# Schematic_Wankler.net
KiCad netlist of a schematic drawn in EasyEDA
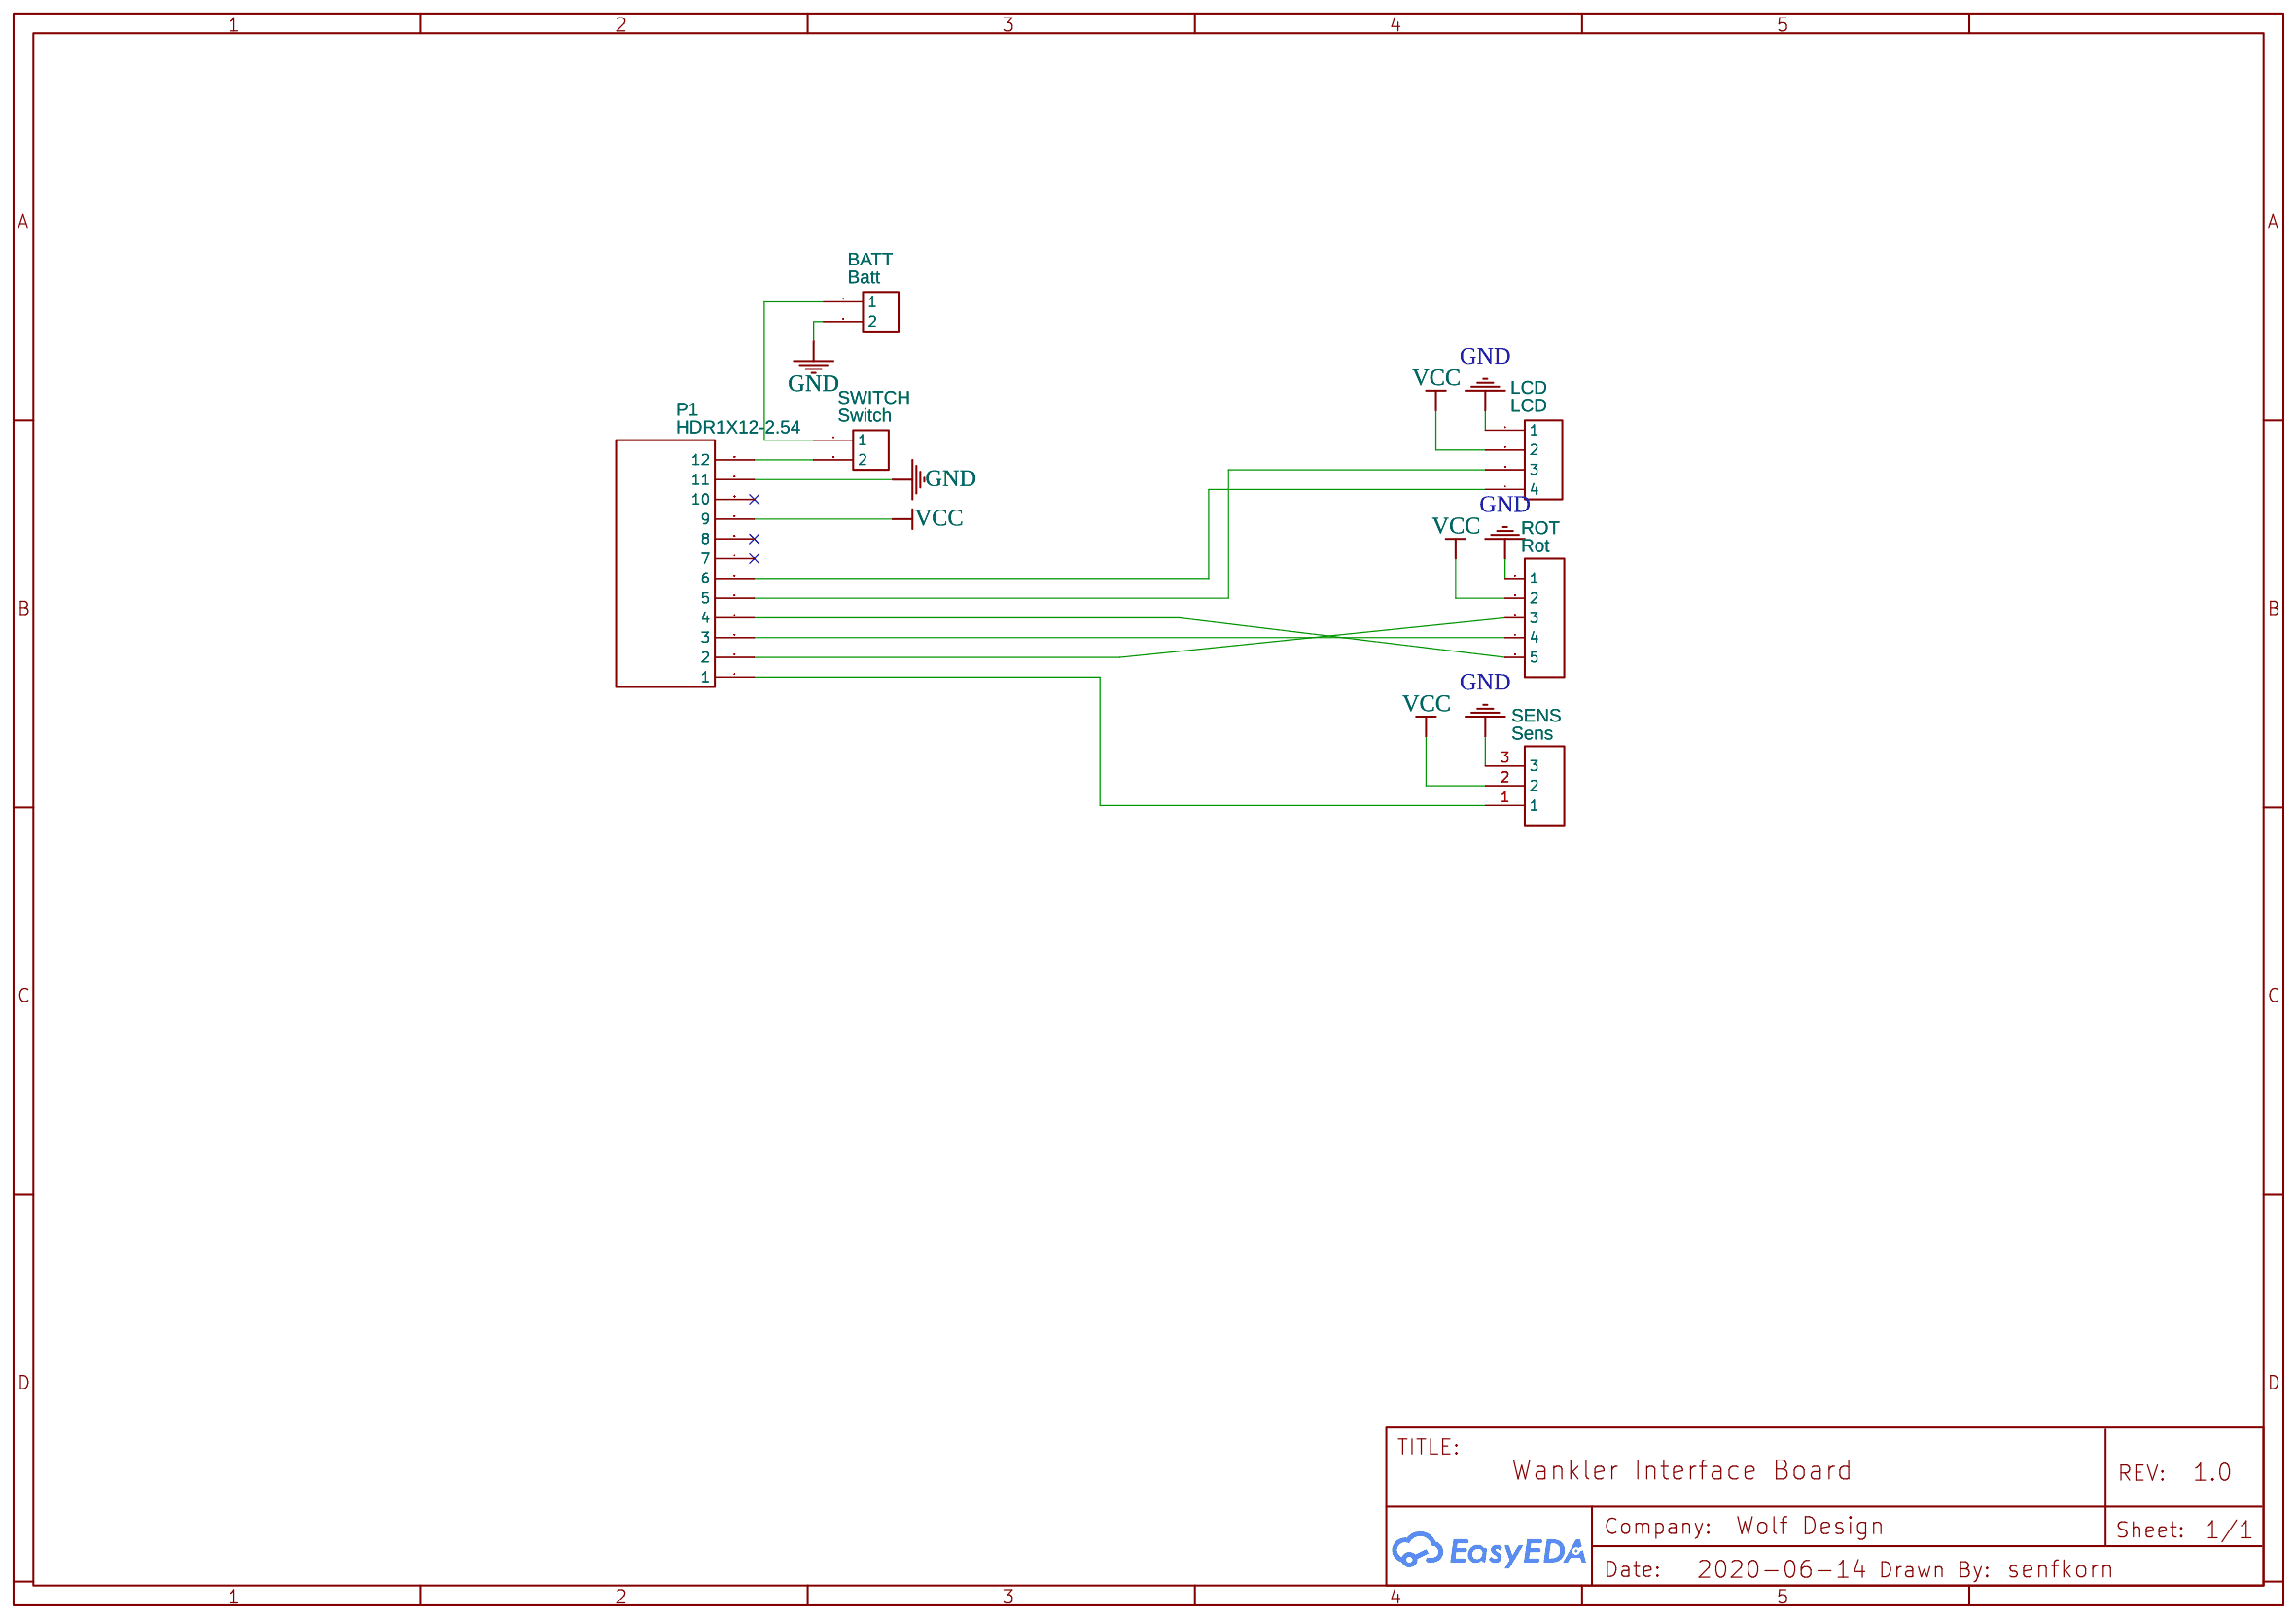
[diagram p0: schematic sheet]

(export (version "E")
  (design (tool "Eeschema 10.0.6"))
  (components
    (comp (ref "BATT") (value "Batt") (libsource (lib "") (part "HDR-2x1/2.54_1")))
    (comp (ref "LCD") (value "LCD") (libsource (lib "") (part "HDR-4x1/2.54")))
    (comp (ref "P1")
      (value "HDR1X12-2.54")
      (fields
        (field (name "BOM_Manufacturer Part") "Female headerHDR1X8-2.54")
        (field (name "BOM_Supplier Part") "C27438")
      )
      (libsource (lib "") (part "HDR1X12-2.54"))
    )
    (comp (ref "ROT")
      (value "Rot")
      (fields
        (field (name "BOM_Manufacturer Part") "2.54mm 1*5p Female header")
        (field (name "BOM_Supplier Part") "C50950")
      )
      (libsource (lib "") (part "HDR-2.54_1x5"))
    )
    (comp (ref "SENS") (value "Sens") (libsource (lib "") (part "HDR-3x1/2.54")))
    (comp (ref "SWITCH") (value "Switch") (libsource (lib "") (part "HDR-2x1/2.54")))
  )
  (nets
    (net (code "1") (name "GND") (class "Default")
      (node (ref "BATT") (pin "2") (pinfunction "2_2") (pintype "input"))
      (node (ref "LCD") (pin "1") (pinfunction "1_1") (pintype "input"))
      (node (ref "P1") (pin "11") (pinfunction "11_11") (pintype "input"))
      (node (ref "ROT") (pin "1") (pinfunction "1_1") (pintype "input"))
      (node (ref "SENS") (pin "3") (pinfunction "3_3") (pintype "unspecified"))
    )
    (net (code "2") (name "Net-(BATT-Pad1)") (class "Default")
      (node (ref "BATT") (pin "1") (pinfunction "1_1") (pintype "input"))
      (node (ref "SWITCH") (pin "1") (pinfunction "1_1") (pintype "input"))
    )
    (net (code "3") (name "Net-(LCD-Pad3)") (class "Default")
      (node (ref "LCD") (pin "3") (pinfunction "3_3") (pintype "input"))
      (node (ref "P1") (pin "5") (pinfunction "5_5") (pintype "input"))
    )
    (net (code "4") (name "Net-(LCD-Pad4)") (class "Default")
      (node (ref "LCD") (pin "4") (pinfunction "4_4") (pintype "input"))
      (node (ref "P1") (pin "6") (pinfunction "6_6") (pintype "input"))
    )
    (net (code "5") (name "Net-(P1-Pad1)") (class "Default")
      (node (ref "P1") (pin "1") (pinfunction "1_1") (pintype "input"))
      (node (ref "SENS") (pin "1") (pinfunction "1_1") (pintype "unspecified"))
    )
    (net (code "6") (name "Net-(P1-Pad2)") (class "Default")
      (node (ref "P1") (pin "2") (pinfunction "2_2") (pintype "input"))
      (node (ref "ROT") (pin "3") (pinfunction "3_3") (pintype "input"))
    )
    (net (code "7") (name "Net-(P1-Pad3)") (class "Default")
      (node (ref "P1") (pin "3") (pinfunction "3_3") (pintype "input"))
      (node (ref "ROT") (pin "4") (pinfunction "4_4") (pintype "input"))
    )
    (net (code "8") (name "Net-(P1-Pad4)") (class "Default")
      (node (ref "P1") (pin "4") (pinfunction "4_4") (pintype "input"))
      (node (ref "ROT") (pin "5") (pinfunction "5_5") (pintype "input"))
    )
    (net (code "9") (name "Net-(P1-Pad12)") (class "Default")
      (node (ref "P1") (pin "12") (pinfunction "12_12") (pintype "input"))
      (node (ref "SWITCH") (pin "2") (pinfunction "2_2") (pintype "input"))
    )
    (net (code "10") (name "VCC") (class "Default")
      (node (ref "LCD") (pin "2") (pinfunction "2_2") (pintype "input"))
      (node (ref "P1") (pin "9") (pinfunction "9_9") (pintype "input"))
      (node (ref "ROT") (pin "2") (pinfunction "2_2") (pintype "input"))
      (node (ref "SENS") (pin "2") (pinfunction "2_2") (pintype "unspecified"))
    )
    (net (code "11") (name "unconnected-(P1-Pad7)") (class "Default")
      (node (ref "P1") (pin "7") (pinfunction "7_7") (pintype "input+no_connect"))
    )
    (net (code "12") (name "unconnected-(P1-Pad8)") (class "Default")
      (node (ref "P1") (pin "8") (pinfunction "8_8") (pintype "input+no_connect"))
    )
    (net (code "13") (name "unconnected-(P1-Pad10)") (class "Default")
      (node (ref "P1") (pin "10") (pinfunction "10_10") (pintype "input+no_connect"))
    )
  )
)
